# USB2Power.net
KiCad netlist of a schematic drawn in EAGLE
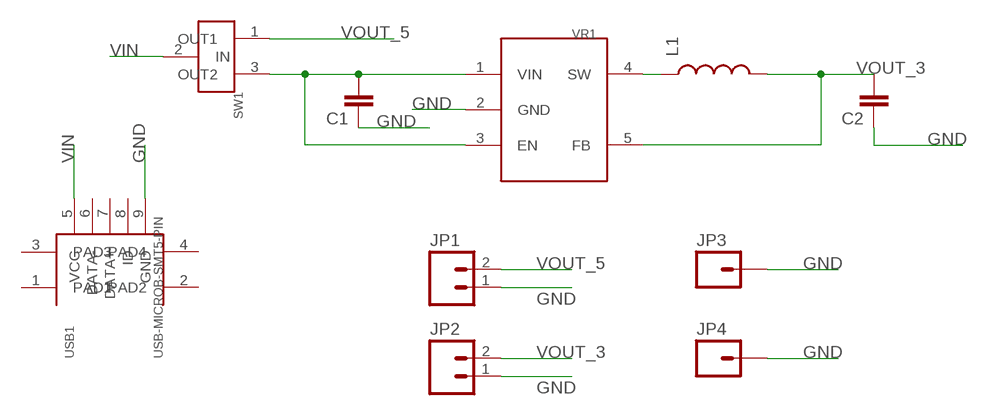
[diagram p0: schematic, sheet 1]

(export (version "E")
  (design (tool "Eeschema 10.0.6"))
  (components
    (comp (ref "C1")
      (value "CAP0603-CAP")
      (footprint "eagle-import:0603-CAP")
      (libsource (lib "eagle-import") (part "CAP0603-CAP"))
    )
    (comp (ref "C2")
      (value "CAP0603-CAP")
      (footprint "eagle-import:0603-CAP")
      (libsource (lib "eagle-import") (part "CAP0603-CAP"))
    )
    (comp (ref "JP1")
      (value "M02PTH")
      (footprint "eagle-import:1X02")
      (libsource (lib "eagle-import") (part "M02PTH"))
    )
    (comp (ref "JP2")
      (value "M02PTH")
      (footprint "eagle-import:1X02")
      (libsource (lib "eagle-import") (part "M02PTH"))
    )
    (comp (ref "JP3")
      (value "M01PTH")
      (footprint "eagle-import:1X01")
      (libsource (lib "eagle-import") (part "M01PTH"))
    )
    (comp (ref "JP4")
      (value "M01PTH")
      (footprint "eagle-import:1X01")
      (libsource (lib "eagle-import") (part "M01PTH"))
    )
    (comp (ref "L1")
      (value "INDUCTOR30OHM,1.8A")
      (footprint "eagle-import:0603")
      (libsource (lib "eagle-import") (part "INDUCTOR30OHM,1.8A"))
    )
    (comp (ref "SW1")
      (value "PCM12SMTR")
      (footprint "eagle-import:PCM12SMTR")
      (libsource (lib "eagle-import") (part "PCM12SMTR"))
    )
    (comp (ref "USB1")
      (value "USB-MICROB-SMT5-PIN")
      (footprint "eagle-import:USB-MICROB-SMT")
      (libsource (lib "eagle-import") (part "USB-MICROB-SMT5-PIN"))
    )
    (comp (ref "VR1")
      (value "ADP2108")
      (footprint "eagle-import:UJ-5_TSOT")
      (libsource (lib "eagle-import") (part "ADP2108"))
    )
  )
  (nets
    (net (code "1") (name "/GND") (class "Default")
      (node (ref "C1") (pin "1") (pinfunction "1_1") (pintype "passive"))
      (node (ref "C2") (pin "1") (pinfunction "1_1") (pintype "passive"))
      (node (ref "JP1") (pin "1") (pinfunction "1_1") (pintype "passive"))
      (node (ref "JP2") (pin "1") (pinfunction "1_1") (pintype "passive"))
      (node (ref "JP3") (pin "1") (pinfunction "1_1") (pintype "passive"))
      (node (ref "JP4") (pin "1") (pinfunction "1_1") (pintype "passive"))
      (node (ref "USB1") (pin "9") (pinfunction "GND_9") (pintype "bidirectional"))
      (node (ref "VR1") (pin "2") (pinfunction "GND_2") (pintype "bidirectional"))
    )
    (net (code "2") (name "/VIN") (class "Default")
      (node (ref "SW1") (pin "2") (pinfunction "IN_2") (pintype "bidirectional"))
      (node (ref "USB1") (pin "5") (pinfunction "VCC_5") (pintype "bidirectional"))
    )
    (net (code "3") (name "/VOUT_3") (class "Default")
      (node (ref "C2") (pin "2") (pinfunction "2_2") (pintype "passive"))
      (node (ref "JP2") (pin "2") (pinfunction "2_2") (pintype "passive"))
      (node (ref "L1") (pin "2") (pinfunction "2_2") (pintype "passive"))
      (node (ref "VR1") (pin "5") (pinfunction "FB_5") (pintype "bidirectional"))
    )
    (net (code "4") (name "/VOUT_5") (class "Default")
      (node (ref "JP1") (pin "2") (pinfunction "2_2") (pintype "passive"))
      (node (ref "SW1") (pin "1") (pinfunction "OUT1_1") (pintype "bidirectional"))
    )
    (net (code "5") (name "Net-(SW1-OUT2)") (class "Default")
      (node (ref "C1") (pin "2") (pinfunction "2_2") (pintype "passive"))
      (node (ref "SW1") (pin "3") (pinfunction "OUT2_3") (pintype "bidirectional"))
      (node (ref "VR1") (pin "1") (pinfunction "VIN_1") (pintype "bidirectional"))
      (node (ref "VR1") (pin "3") (pinfunction "EN_3") (pintype "bidirectional"))
    )
    (net (code "6") (name "Net-(VR1-SW)") (class "Default")
      (node (ref "L1") (pin "1") (pinfunction "1_1") (pintype "passive"))
      (node (ref "VR1") (pin "4") (pinfunction "SW_4") (pintype "bidirectional"))
    )
    (net (code "7") (name "unconnected-(USB1-DATA+-Pad7)") (class "Default")
      (node (ref "USB1") (pin "7") (pinfunction "DATA+_7") (pintype "bidirectional"))
    )
    (net (code "8") (name "unconnected-(USB1-DATA--Pad6)") (class "Default")
      (node (ref "USB1") (pin "6") (pinfunction "DATA-_6") (pintype "bidirectional"))
    )
    (net (code "9") (name "unconnected-(USB1-ID-Pad8)") (class "Default")
      (node (ref "USB1") (pin "8") (pinfunction "ID_8") (pintype "bidirectional"))
    )
    (net (code "10") (name "unconnected-(USB1-PAD1-Pad1)") (class "Default")
      (node (ref "USB1") (pin "1") (pinfunction "PAD1_1") (pintype "no_connect"))
    )
    (net (code "11") (name "unconnected-(USB1-PAD2-Pad2)") (class "Default")
      (node (ref "USB1") (pin "2") (pinfunction "PAD2_2") (pintype "no_connect"))
    )
    (net (code "12") (name "unconnected-(USB1-PAD3-Pad3)") (class "Default")
      (node (ref "USB1") (pin "3") (pinfunction "PAD3_3") (pintype "no_connect"))
    )
    (net (code "13") (name "unconnected-(USB1-PAD4-Pad4)") (class "Default")
      (node (ref "USB1") (pin "4") (pinfunction "PAD4_4") (pintype "no_connect"))
    )
  )
)
